# Sheet1.net
KiCad netlist of a schematic drawn in Altium Designer
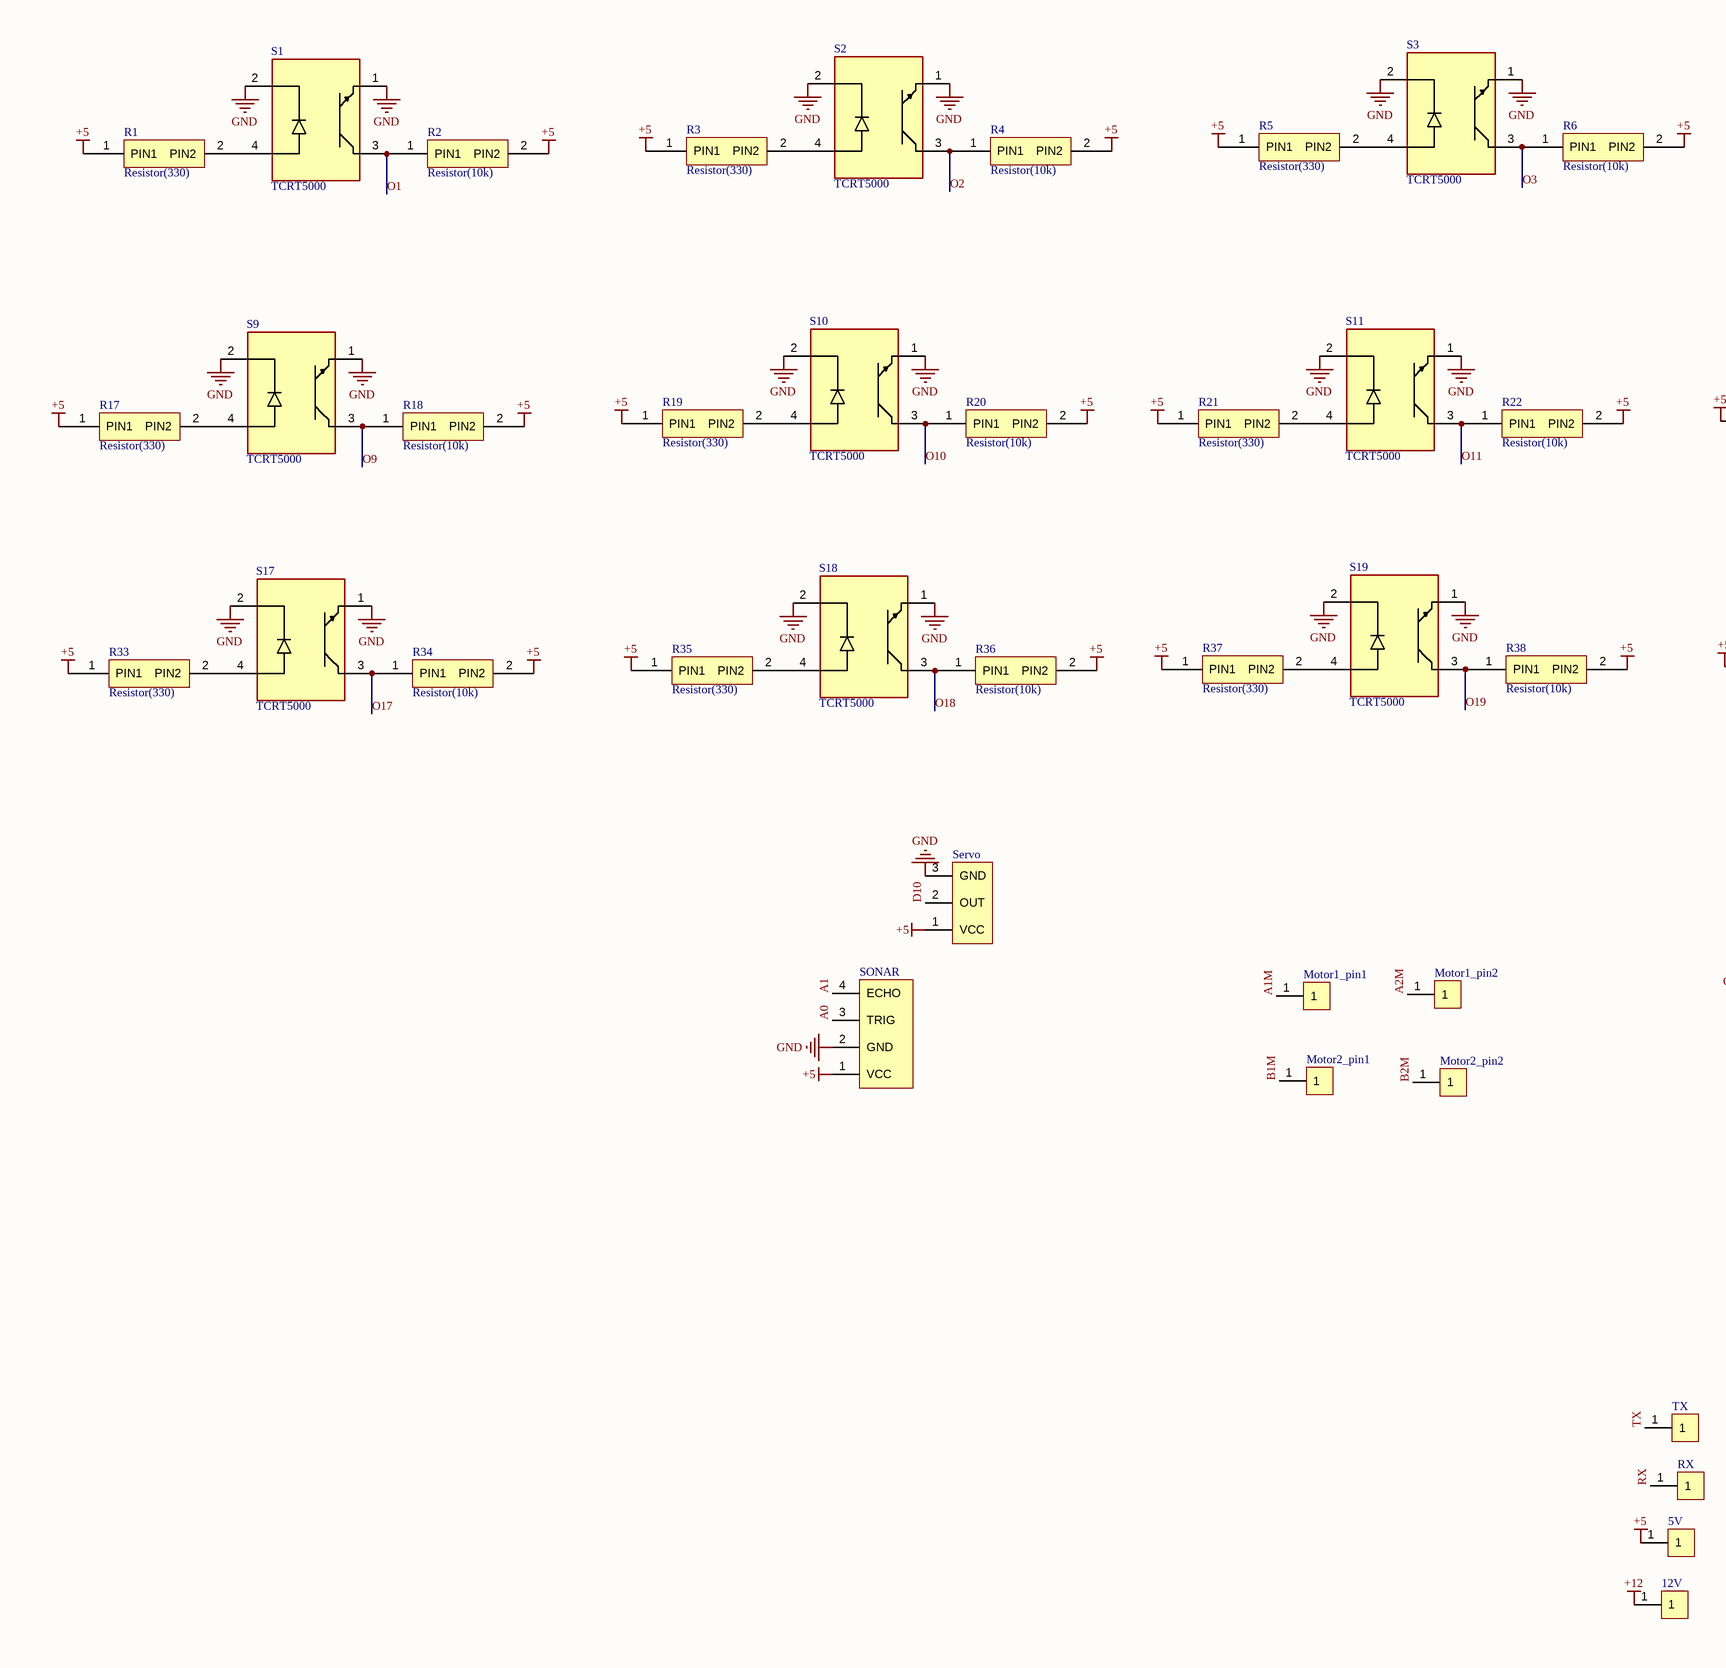
[diagram p0: Sheet1.SchDoc, left]
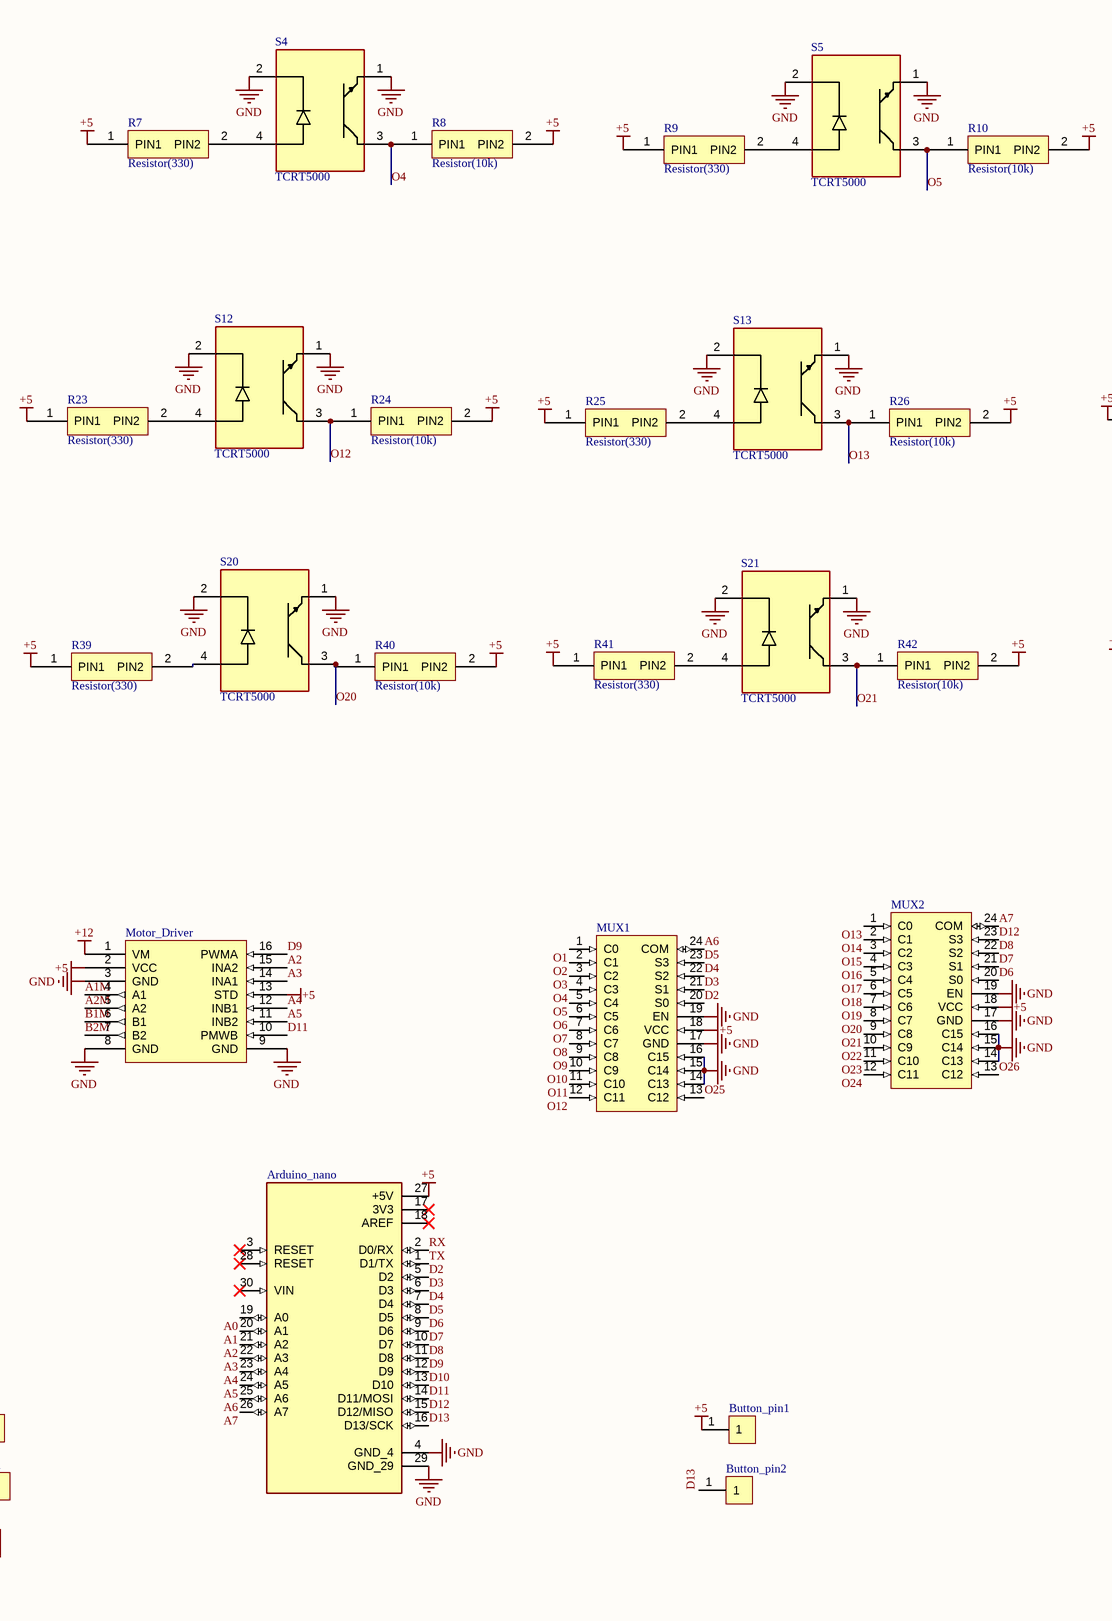
[diagram p1: Sheet1.SchDoc, middle]
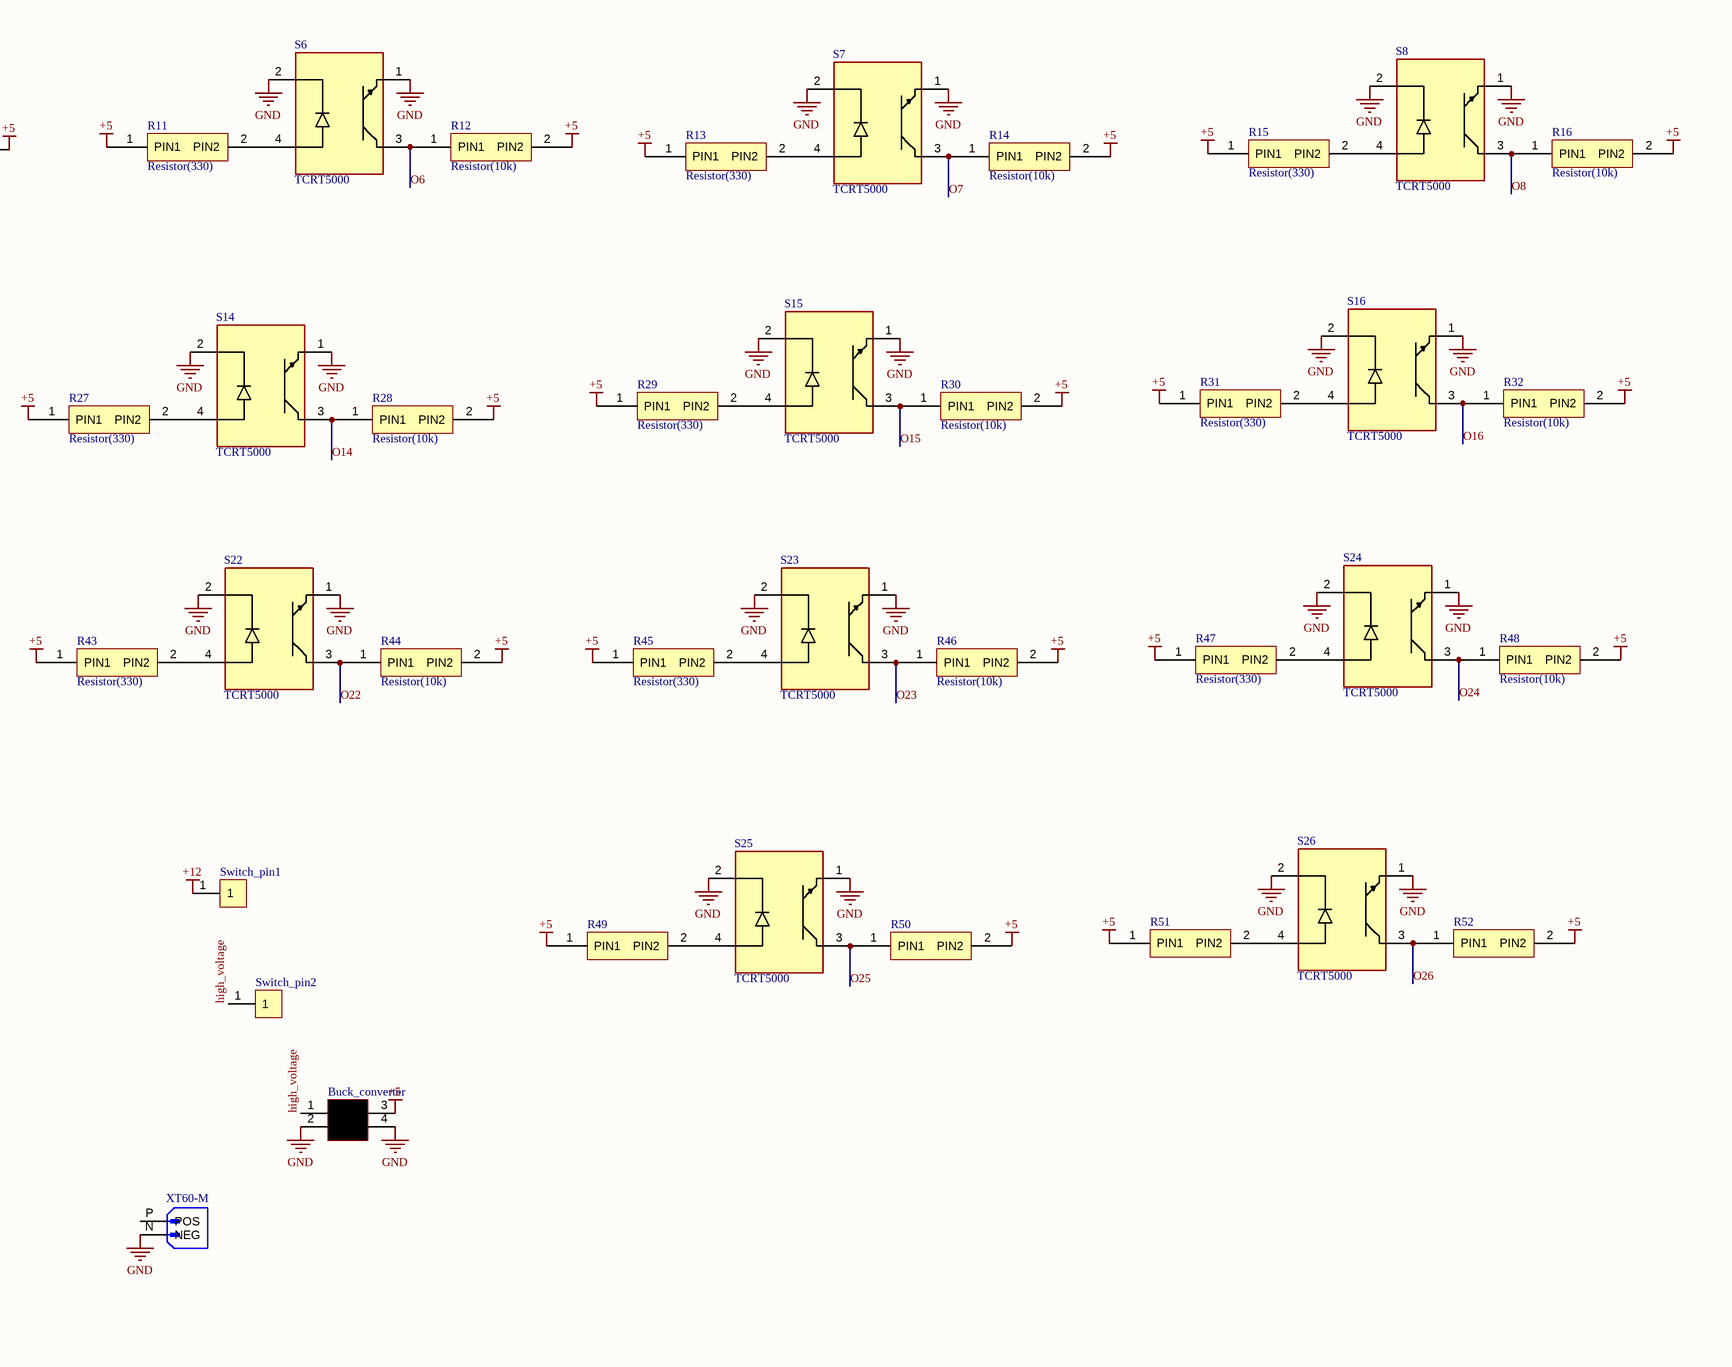
[diagram p2: Sheet1.SchDoc, right]

(export (version "E")
  (design (tool "Eeschema 10.0.6"))
  (components
    (comp (ref "5V")
      (value "~")
      (footprint "1_pin_male_header")
      (libsource (lib "newer") (part "1_pin_male_header"))
    )
    (comp (ref "12V")
      (value "~")
      (footprint "1_pin_male_header")
      (libsource (lib "newer") (part "1_pin_male_header"))
    )
    (comp (ref "Arduino_nano")
      (value "~")
      (footprint "Arduino_nano")
      (libsource (lib "newer") (part "Arduino_nano"))
    )
    (comp (ref "Buck_converter")
      (value "~")
      (footprint "Buck_converter")
      (libsource (lib "newer") (part "Buck_converter"))
    )
    (comp (ref "Button_pin1")
      (value "~")
      (footprint "1_pin_female_header")
      (libsource (lib "newer") (part "1_pin_female_header"))
    )
    (comp (ref "Button_pin2")
      (value "~")
      (footprint "1_pin_female_header")
      (libsource (lib "newer") (part "1_pin_female_header"))
    )
    (comp (ref "Motor1_pin1")
      (value "~")
      (footprint "1_pin_male_header")
      (libsource (lib "newer") (part "1_pin_male_header"))
    )
    (comp (ref "Motor1_pin2")
      (value "~")
      (footprint "1_pin_male_header")
      (libsource (lib "newer") (part "1_pin_male_header"))
    )
    (comp (ref "Motor2_pin1")
      (value "~")
      (footprint "1_pin_male_header")
      (libsource (lib "newer") (part "1_pin_male_header"))
    )
    (comp (ref "Motor2_pin2")
      (value "~")
      (footprint "1_pin_male_header")
      (libsource (lib "newer") (part "1_pin_male_header"))
    )
    (comp (ref "Motor_Driver")
      (value "~")
      (footprint "TB6612_Motor_driver")
      (libsource (lib "newer") (part "TB6612_Motor_driver"))
    )
    (comp (ref "MUX1") (value "~") (footprint "MUX") (libsource (lib "newer") (part "MUX")))
    (comp (ref "MUX2") (value "~") (footprint "MUX") (libsource (lib "newer") (part "MUX")))
    (comp (ref "R1")
      (value "Resistor(330)")
      (footprint "Resistor(330)")
      (libsource (lib "newer") (part "Resistor(330)"))
    )
    (comp (ref "R2")
      (value "Resistor(10k)")
      (footprint "Resistor(10k)")
      (libsource (lib "newer") (part "Resistor(10k)"))
    )
    (comp (ref "R3")
      (value "Resistor(330)")
      (footprint "Resistor(330)")
      (libsource (lib "newer") (part "Resistor(330)"))
    )
    (comp (ref "R4")
      (value "Resistor(10k)")
      (footprint "Resistor(10k)")
      (libsource (lib "newer") (part "Resistor(10k)"))
    )
    (comp (ref "R5")
      (value "Resistor(330)")
      (footprint "Resistor(330)")
      (libsource (lib "newer") (part "Resistor(330)"))
    )
    (comp (ref "R6")
      (value "Resistor(10k)")
      (footprint "Resistor(10k)")
      (libsource (lib "newer") (part "Resistor(10k)"))
    )
    (comp (ref "R7")
      (value "Resistor(330)")
      (footprint "Resistor(330)")
      (libsource (lib "newer") (part "Resistor(330)"))
    )
    (comp (ref "R8")
      (value "Resistor(10k)")
      (footprint "Resistor(10k)")
      (libsource (lib "newer") (part "Resistor(10k)"))
    )
    (comp (ref "R9")
      (value "Resistor(330)")
      (footprint "Resistor(330)")
      (libsource (lib "newer") (part "Resistor(330)"))
    )
    (comp (ref "R10")
      (value "Resistor(10k)")
      (footprint "Resistor(10k)")
      (libsource (lib "newer") (part "Resistor(10k)"))
    )
    (comp (ref "R11")
      (value "Resistor(330)")
      (footprint "Resistor(330)")
      (libsource (lib "newer") (part "Resistor(330)"))
    )
    (comp (ref "R12")
      (value "Resistor(10k)")
      (footprint "Resistor(10k)")
      (libsource (lib "newer") (part "Resistor(10k)"))
    )
    (comp (ref "R13")
      (value "Resistor(330)")
      (footprint "Resistor(330)")
      (libsource (lib "newer") (part "Resistor(330)"))
    )
    (comp (ref "R14")
      (value "Resistor(10k)")
      (footprint "Resistor(10k)")
      (libsource (lib "newer") (part "Resistor(10k)"))
    )
    (comp (ref "R15")
      (value "Resistor(330)")
      (footprint "Resistor(330)")
      (libsource (lib "newer") (part "Resistor(330)"))
    )
    (comp (ref "R16")
      (value "Resistor(10k)")
      (footprint "Resistor(10k)")
      (libsource (lib "newer") (part "Resistor(10k)"))
    )
    (comp (ref "R17")
      (value "Resistor(330)")
      (footprint "Resistor(330)")
      (libsource (lib "newer") (part "Resistor(330)"))
    )
    (comp (ref "R18")
      (value "Resistor(10k)")
      (footprint "Resistor(10k)")
      (libsource (lib "newer") (part "Resistor(10k)"))
    )
    (comp (ref "R19")
      (value "Resistor(330)")
      (footprint "Resistor(330)")
      (libsource (lib "newer") (part "Resistor(330)"))
    )
    (comp (ref "R20")
      (value "Resistor(10k)")
      (footprint "Resistor(10k)")
      (libsource (lib "newer") (part "Resistor(10k)"))
    )
    (comp (ref "R21")
      (value "Resistor(330)")
      (footprint "Resistor(330)")
      (libsource (lib "newer") (part "Resistor(330)"))
    )
    (comp (ref "R22")
      (value "Resistor(10k)")
      (footprint "Resistor(10k)")
      (libsource (lib "newer") (part "Resistor(10k)"))
    )
    (comp (ref "R23")
      (value "Resistor(330)")
      (footprint "Resistor(330)")
      (libsource (lib "newer") (part "Resistor(330)"))
    )
    (comp (ref "R24")
      (value "Resistor(10k)")
      (footprint "Resistor(10k)")
      (libsource (lib "newer") (part "Resistor(10k)"))
    )
    (comp (ref "R25")
      (value "Resistor(330)")
      (footprint "Resistor(330)")
      (libsource (lib "newer") (part "Resistor(330)"))
    )
    (comp (ref "R26")
      (value "Resistor(10k)")
      (footprint "Resistor(10k)")
      (libsource (lib "newer") (part "Resistor(10k)"))
    )
    (comp (ref "R27")
      (value "Resistor(330)")
      (footprint "Resistor(330)")
      (libsource (lib "newer") (part "Resistor(330)"))
    )
    (comp (ref "R28")
      (value "Resistor(10k)")
      (footprint "Resistor(10k)")
      (libsource (lib "newer") (part "Resistor(10k)"))
    )
    (comp (ref "R29")
      (value "Resistor(330)")
      (footprint "Resistor(330)")
      (libsource (lib "newer") (part "Resistor(330)"))
    )
    (comp (ref "R30")
      (value "Resistor(10k)")
      (footprint "Resistor(10k)")
      (libsource (lib "newer") (part "Resistor(10k)"))
    )
    (comp (ref "R31")
      (value "Resistor(330)")
      (footprint "Resistor(330)")
      (libsource (lib "newer") (part "Resistor(330)"))
    )
    (comp (ref "R32")
      (value "Resistor(10k)")
      (footprint "Resistor(10k)")
      (libsource (lib "newer") (part "Resistor(10k)"))
    )
    (comp (ref "R33")
      (value "Resistor(330)")
      (footprint "Resistor(330)")
      (libsource (lib "newer") (part "Resistor(330)"))
    )
    (comp (ref "R34")
      (value "Resistor(10k)")
      (footprint "Resistor(10k)")
      (libsource (lib "newer") (part "Resistor(10k)"))
    )
    (comp (ref "R35")
      (value "Resistor(330)")
      (footprint "Resistor(330)")
      (libsource (lib "newer") (part "Resistor(330)"))
    )
    (comp (ref "R36")
      (value "Resistor(10k)")
      (footprint "Resistor(10k)")
      (libsource (lib "newer") (part "Resistor(10k)"))
    )
    (comp (ref "R37")
      (value "Resistor(330)")
      (footprint "Resistor(330)")
      (libsource (lib "newer") (part "Resistor(330)"))
    )
    (comp (ref "R38")
      (value "Resistor(10k)")
      (footprint "Resistor(10k)")
      (libsource (lib "newer") (part "Resistor(10k)"))
    )
    (comp (ref "R39")
      (value "Resistor(330)")
      (footprint "Resistor(330)")
      (libsource (lib "newer") (part "Resistor(330)"))
    )
    (comp (ref "R40")
      (value "Resistor(10k)")
      (footprint "Resistor(10k)")
      (libsource (lib "newer") (part "Resistor(10k)"))
    )
    (comp (ref "R41")
      (value "Resistor(330)")
      (footprint "Resistor(330)")
      (libsource (lib "newer") (part "Resistor(330)"))
    )
    (comp (ref "R42")
      (value "Resistor(10k)")
      (footprint "Resistor(10k)")
      (libsource (lib "newer") (part "Resistor(10k)"))
    )
    (comp (ref "R43")
      (value "Resistor(330)")
      (footprint "Resistor(330)")
      (libsource (lib "newer") (part "Resistor(330)"))
    )
    (comp (ref "R44")
      (value "Resistor(10k)")
      (footprint "Resistor(10k)")
      (libsource (lib "newer") (part "Resistor(10k)"))
    )
    (comp (ref "R45")
      (value "Resistor(330)")
      (footprint "Resistor(330)")
      (libsource (lib "newer") (part "Resistor(330)"))
    )
    (comp (ref "R46")
      (value "Resistor(10k)")
      (footprint "Resistor(10k)")
      (libsource (lib "newer") (part "Resistor(10k)"))
    )
    (comp (ref "R47")
      (value "Resistor(330)")
      (footprint "Resistor(330)")
      (libsource (lib "newer") (part "Resistor(330)"))
    )
    (comp (ref "R48")
      (value "Resistor(10k)")
      (footprint "Resistor(10k)")
      (libsource (lib "newer") (part "Resistor(10k)"))
    )
    (comp (ref "R49")
      (value "~")
      (footprint "Resistor(330)")
      (libsource (lib "newer") (part "Resistor(330)"))
    )
    (comp (ref "R50")
      (value "~")
      (footprint "Resistor(10k)")
      (libsource (lib "newer") (part "Resistor(10k)"))
    )
    (comp (ref "R51")
      (value "~")
      (footprint "Resistor(330)")
      (libsource (lib "newer") (part "Resistor(330)"))
    )
    (comp (ref "R52")
      (value "~")
      (footprint "Resistor(10k)")
      (libsource (lib "newer") (part "Resistor(10k)"))
    )
    (comp (ref "RX")
      (value "~")
      (footprint "1_pin_male_header")
      (libsource (lib "newer") (part "1_pin_male_header"))
    )
    (comp (ref "S1") (value "TCRT5000") (footprint "TCRT5000") (libsource (lib "newer") (part "TCRT5000")))
    (comp (ref "S2") (value "TCRT5000") (footprint "TCRT5000") (libsource (lib "newer") (part "TCRT5000")))
    (comp (ref "S3") (value "TCRT5000") (footprint "TCRT5000") (libsource (lib "newer") (part "TCRT5000")))
    (comp (ref "S4") (value "TCRT5000") (footprint "TCRT5000") (libsource (lib "newer") (part "TCRT5000")))
    (comp (ref "S5") (value "TCRT5000") (footprint "TCRT5000") (libsource (lib "newer") (part "TCRT5000")))
    (comp (ref "S6") (value "TCRT5000") (footprint "TCRT5000") (libsource (lib "newer") (part "TCRT5000")))
    (comp (ref "S7") (value "TCRT5000") (footprint "TCRT5000") (libsource (lib "newer") (part "TCRT5000")))
    (comp (ref "S8") (value "TCRT5000") (footprint "TCRT5000") (libsource (lib "newer") (part "TCRT5000")))
    (comp (ref "S9") (value "TCRT5000") (footprint "TCRT5000") (libsource (lib "newer") (part "TCRT5000")))
    (comp (ref "S10") (value "TCRT5000") (footprint "TCRT5000") (libsource (lib "newer") (part "TCRT5000")))
    (comp (ref "S11") (value "TCRT5000") (footprint "TCRT5000") (libsource (lib "newer") (part "TCRT5000")))
    (comp (ref "S12") (value "TCRT5000") (footprint "TCRT5000") (libsource (lib "newer") (part "TCRT5000")))
    (comp (ref "S13") (value "TCRT5000") (footprint "TCRT5000") (libsource (lib "newer") (part "TCRT5000")))
    (comp (ref "S14") (value "TCRT5000") (footprint "TCRT5000") (libsource (lib "newer") (part "TCRT5000")))
    (comp (ref "S15") (value "TCRT5000") (footprint "TCRT5000") (libsource (lib "newer") (part "TCRT5000")))
    (comp (ref "S16") (value "TCRT5000") (footprint "TCRT5000") (libsource (lib "newer") (part "TCRT5000")))
    (comp (ref "S17") (value "TCRT5000") (footprint "TCRT5000") (libsource (lib "newer") (part "TCRT5000")))
    (comp (ref "S18") (value "TCRT5000") (footprint "TCRT5000") (libsource (lib "newer") (part "TCRT5000")))
    (comp (ref "S19") (value "TCRT5000") (footprint "TCRT5000") (libsource (lib "newer") (part "TCRT5000")))
    (comp (ref "S20") (value "TCRT5000") (footprint "TCRT5000") (libsource (lib "newer") (part "TCRT5000")))
    (comp (ref "S21") (value "TCRT5000") (footprint "TCRT5000") (libsource (lib "newer") (part "TCRT5000")))
    (comp (ref "S22") (value "TCRT5000") (footprint "TCRT5000") (libsource (lib "newer") (part "TCRT5000")))
    (comp (ref "S23") (value "TCRT5000") (footprint "TCRT5000") (libsource (lib "newer") (part "TCRT5000")))
    (comp (ref "S24") (value "TCRT5000") (footprint "TCRT5000") (libsource (lib "newer") (part "TCRT5000")))
    (comp (ref "S25") (value "TCRT5000") (footprint "TCRT5000") (libsource (lib "newer") (part "TCRT5000")))
    (comp (ref "S26") (value "TCRT5000") (footprint "TCRT5000") (libsource (lib "newer") (part "TCRT5000")))
    (comp (ref "Servo")
      (value "~")
      (footprint "3_pin_male_header")
      (libsource (lib "newer") (part "3_pin_male_header"))
    )
    (comp (ref "SONAR") (value "~") (footprint "4 pin male") (libsource (lib "lfr_nano") (part "4 pin male")))
    (comp (ref "Switch_pin1")
      (value "~")
      (footprint "1_pin_male_header")
      (libsource (lib "newer") (part "1_pin_male_header"))
    )
    (comp (ref "Switch_pin2")
      (value "~")
      (footprint "1_pin_male_header")
      (libsource (lib "newer") (part "1_pin_male_header"))
    )
    (comp (ref "TX")
      (value "~")
      (footprint "1_pin_male_header")
      (libsource (lib "newer") (part "1_pin_male_header"))
    )
    (comp (ref "XT60-M")
      (value "~")
      (footprint "AMASS_XT60-M")
      (description "Plug; DC supply; XT60; male; PIN: 2; for cable; soldered; 30A; 500V")
      (fields (field (name "MF") "AMASS") (field (name "MP") "XT60-M"))
      (libsource (lib "XT60-M") (part "XT60-M"))
    )
  )
  (nets
    (net (code "1") (name "+5") (class "Default")
      (node (ref "5V") (pin "1") (pinfunction "1_1") (pintype "passive"))
      (node (ref "Arduino_nano") (pin "27") (pinfunction "+5V_27") (pintype "power_in"))
      (node (ref "Buck_converter") (pin "3") (pinfunction "3_3") (pintype "passive"))
      (node (ref "Button_pin1") (pin "1") (pinfunction "1_1") (pintype "passive"))
      (node (ref "MUX1") (pin "18") (pinfunction "VCC_18") (pintype "input"))
      (node (ref "MUX2") (pin "18") (pinfunction "VCC_18") (pintype "input"))
      (node (ref "Motor_Driver") (pin "13") (pinfunction "STD_13") (pintype "input"))
      (node (ref "Motor_Driver") (pin "2") (pinfunction "VCC_2") (pintype "power_in"))
      (node (ref "R1") (pin "1") (pinfunction "PIN1_1") (pintype "passive"))
      (node (ref "R10") (pin "2") (pinfunction "PIN2_2") (pintype "passive"))
      (node (ref "R11") (pin "1") (pinfunction "PIN1_1") (pintype "passive"))
      (node (ref "R12") (pin "2") (pinfunction "PIN2_2") (pintype "passive"))
      (node (ref "R13") (pin "1") (pinfunction "PIN1_1") (pintype "passive"))
      (node (ref "R14") (pin "2") (pinfunction "PIN2_2") (pintype "passive"))
      (node (ref "R15") (pin "1") (pinfunction "PIN1_1") (pintype "passive"))
      (node (ref "R16") (pin "2") (pinfunction "PIN2_2") (pintype "passive"))
      (node (ref "R17") (pin "1") (pinfunction "PIN1_1") (pintype "passive"))
      (node (ref "R18") (pin "2") (pinfunction "PIN2_2") (pintype "passive"))
      (node (ref "R19") (pin "1") (pinfunction "PIN1_1") (pintype "passive"))
      (node (ref "R2") (pin "2") (pinfunction "PIN2_2") (pintype "passive"))
      (node (ref "R20") (pin "2") (pinfunction "PIN2_2") (pintype "passive"))
      (node (ref "R21") (pin "1") (pinfunction "PIN1_1") (pintype "passive"))
      (node (ref "R22") (pin "2") (pinfunction "PIN2_2") (pintype "passive"))
      (node (ref "R23") (pin "1") (pinfunction "PIN1_1") (pintype "passive"))
      (node (ref "R24") (pin "2") (pinfunction "PIN2_2") (pintype "passive"))
      (node (ref "R25") (pin "1") (pinfunction "PIN1_1") (pintype "passive"))
      (node (ref "R26") (pin "2") (pinfunction "PIN2_2") (pintype "passive"))
      (node (ref "R27") (pin "1") (pinfunction "PIN1_1") (pintype "passive"))
      (node (ref "R28") (pin "2") (pinfunction "PIN2_2") (pintype "passive"))
      (node (ref "R29") (pin "1") (pinfunction "PIN1_1") (pintype "passive"))
      (node (ref "R3") (pin "1") (pinfunction "PIN1_1") (pintype "passive"))
      (node (ref "R30") (pin "2") (pinfunction "PIN2_2") (pintype "passive"))
      (node (ref "R31") (pin "1") (pinfunction "PIN1_1") (pintype "passive"))
      (node (ref "R32") (pin "2") (pinfunction "PIN2_2") (pintype "passive"))
      (node (ref "R33") (pin "1") (pinfunction "PIN1_1") (pintype "passive"))
      (node (ref "R34") (pin "2") (pinfunction "PIN2_2") (pintype "passive"))
      (node (ref "R35") (pin "1") (pinfunction "PIN1_1") (pintype "passive"))
      (node (ref "R36") (pin "2") (pinfunction "PIN2_2") (pintype "passive"))
      (node (ref "R37") (pin "1") (pinfunction "PIN1_1") (pintype "passive"))
      (node (ref "R38") (pin "2") (pinfunction "PIN2_2") (pintype "passive"))
      (node (ref "R39") (pin "1") (pinfunction "PIN1_1") (pintype "passive"))
      (node (ref "R4") (pin "2") (pinfunction "PIN2_2") (pintype "passive"))
      (node (ref "R40") (pin "2") (pinfunction "PIN2_2") (pintype "passive"))
      (node (ref "R41") (pin "1") (pinfunction "PIN1_1") (pintype "passive"))
      (node (ref "R42") (pin "2") (pinfunction "PIN2_2") (pintype "passive"))
      (node (ref "R43") (pin "1") (pinfunction "PIN1_1") (pintype "passive"))
      (node (ref "R44") (pin "2") (pinfunction "PIN2_2") (pintype "passive"))
      (node (ref "R45") (pin "1") (pinfunction "PIN1_1") (pintype "passive"))
      (node (ref "R46") (pin "2") (pinfunction "PIN2_2") (pintype "passive"))
      (node (ref "R47") (pin "1") (pinfunction "PIN1_1") (pintype "passive"))
      (node (ref "R48") (pin "2") (pinfunction "PIN2_2") (pintype "passive"))
      (node (ref "R49") (pin "1") (pinfunction "PIN1_1") (pintype "passive"))
      (node (ref "R5") (pin "1") (pinfunction "PIN1_1") (pintype "passive"))
      (node (ref "R50") (pin "2") (pinfunction "PIN2_2") (pintype "passive"))
      (node (ref "R51") (pin "1") (pinfunction "PIN1_1") (pintype "passive"))
      (node (ref "R52") (pin "2") (pinfunction "PIN2_2") (pintype "passive"))
      (node (ref "R6") (pin "2") (pinfunction "PIN2_2") (pintype "passive"))
      (node (ref "R7") (pin "1") (pinfunction "PIN1_1") (pintype "passive"))
      (node (ref "R8") (pin "2") (pinfunction "PIN2_2") (pintype "passive"))
      (node (ref "R9") (pin "1") (pinfunction "PIN1_1") (pintype "passive"))
      (node (ref "SONAR") (pin "1") (pinfunction "VCC_1") (pintype "passive"))
      (node (ref "Servo") (pin "1") (pinfunction "VCC_1") (pintype "passive"))
    )
    (net (code "2") (name "+12") (class "Default")
      (node (ref "12V") (pin "1") (pinfunction "1_1") (pintype "passive"))
      (node (ref "Motor_Driver") (pin "1") (pinfunction "VM_1") (pintype "power_in"))
      (node (ref "Switch_pin1") (pin "1") (pinfunction "1_1") (pintype "passive"))
    )
    (net (code "3") (name "/A0") (class "Default")
      (node (ref "Arduino_nano") (pin "19") (pinfunction "A0_19") (pintype "bidirectional"))
      (node (ref "SONAR") (pin "3") (pinfunction "TRIG_3") (pintype "passive"))
    )
    (net (code "4") (name "/A1") (class "Default")
      (node (ref "Arduino_nano") (pin "20") (pinfunction "A1_20") (pintype "bidirectional"))
      (node (ref "SONAR") (pin "4") (pinfunction "ECHO_4") (pintype "passive"))
    )
    (net (code "5") (name "/A1M") (class "Default")
      (node (ref "Motor1_pin1") (pin "1") (pinfunction "1_1") (pintype "passive"))
      (node (ref "Motor_Driver") (pin "4") (pinfunction "A1_4") (pintype "output"))
    )
    (net (code "6") (name "/A2") (class "Default")
      (node (ref "Arduino_nano") (pin "21") (pinfunction "A2_21") (pintype "bidirectional"))
      (node (ref "Motor_Driver") (pin "15") (pinfunction "INA2_15") (pintype "input"))
    )
    (net (code "7") (name "/A2M") (class "Default")
      (node (ref "Motor1_pin2") (pin "1") (pinfunction "1_1") (pintype "passive"))
      (node (ref "Motor_Driver") (pin "5") (pinfunction "A2_5") (pintype "output"))
    )
    (net (code "8") (name "/A3") (class "Default")
      (node (ref "Arduino_nano") (pin "22") (pinfunction "A3_22") (pintype "bidirectional"))
      (node (ref "Motor_Driver") (pin "14") (pinfunction "INA1_14") (pintype "input"))
    )
    (net (code "9") (name "/A4") (class "Default")
      (node (ref "Arduino_nano") (pin "23") (pinfunction "A4_23") (pintype "bidirectional"))
      (node (ref "Motor_Driver") (pin "12") (pinfunction "INB1_12") (pintype "input"))
    )
    (net (code "10") (name "/A5") (class "Default")
      (node (ref "Arduino_nano") (pin "24") (pinfunction "A5_24") (pintype "bidirectional"))
      (node (ref "Motor_Driver") (pin "11") (pinfunction "INB2_11") (pintype "input"))
    )
    (net (code "11") (name "/A6") (class "Default")
      (node (ref "Arduino_nano") (pin "25") (pinfunction "A6_25") (pintype "bidirectional"))
      (node (ref "MUX1") (pin "24") (pinfunction "COM_24") (pintype "bidirectional"))
    )
    (net (code "12") (name "/A7") (class "Default")
      (node (ref "Arduino_nano") (pin "26") (pinfunction "A7_26") (pintype "bidirectional"))
      (node (ref "MUX2") (pin "24") (pinfunction "COM_24") (pintype "bidirectional"))
    )
    (net (code "13") (name "/B1M") (class "Default")
      (node (ref "Motor2_pin1") (pin "1") (pinfunction "1_1") (pintype "passive"))
      (node (ref "Motor_Driver") (pin "6") (pinfunction "B1_6") (pintype "output"))
    )
    (net (code "14") (name "/B2M") (class "Default")
      (node (ref "Motor2_pin2") (pin "1") (pinfunction "1_1") (pintype "passive"))
      (node (ref "Motor_Driver") (pin "7") (pinfunction "B2_7") (pintype "output"))
    )
    (net (code "15") (name "/D2") (class "Default")
      (node (ref "Arduino_nano") (pin "5") (pinfunction "D2_5") (pintype "bidirectional"))
      (node (ref "MUX1") (pin "20") (pinfunction "S0_20") (pintype "input"))
    )
    (net (code "16") (name "/D3") (class "Default")
      (node (ref "Arduino_nano") (pin "6") (pinfunction "D3_6") (pintype "bidirectional"))
      (node (ref "MUX1") (pin "21") (pinfunction "S1_21") (pintype "input"))
    )
    (net (code "17") (name "/D4") (class "Default")
      (node (ref "Arduino_nano") (pin "7") (pinfunction "D4_7") (pintype "bidirectional"))
      (node (ref "MUX1") (pin "22") (pinfunction "S2_22") (pintype "input"))
    )
    (net (code "18") (name "/D5") (class "Default")
      (node (ref "Arduino_nano") (pin "8") (pinfunction "D5_8") (pintype "bidirectional"))
      (node (ref "MUX1") (pin "23") (pinfunction "S3_23") (pintype "input"))
    )
    (net (code "19") (name "/D6") (class "Default")
      (node (ref "Arduino_nano") (pin "9") (pinfunction "D6_9") (pintype "bidirectional"))
      (node (ref "MUX2") (pin "20") (pinfunction "S0_20") (pintype "input"))
    )
    (net (code "20") (name "/D7") (class "Default")
      (node (ref "Arduino_nano") (pin "10") (pinfunction "D7_10") (pintype "bidirectional"))
      (node (ref "MUX2") (pin "21") (pinfunction "S1_21") (pintype "input"))
    )
    (net (code "21") (name "/D8") (class "Default")
      (node (ref "Arduino_nano") (pin "11") (pinfunction "D8_11") (pintype "bidirectional"))
      (node (ref "MUX2") (pin "22") (pinfunction "S2_22") (pintype "input"))
    )
    (net (code "22") (name "/D9") (class "Default")
      (node (ref "Arduino_nano") (pin "12") (pinfunction "D9_12") (pintype "bidirectional"))
      (node (ref "Motor_Driver") (pin "16") (pinfunction "PWMA_16") (pintype "input"))
    )
    (net (code "23") (name "/D10") (class "Default")
      (node (ref "Arduino_nano") (pin "13") (pinfunction "D10_13") (pintype "bidirectional"))
      (node (ref "Servo") (pin "2") (pinfunction "OUT_2") (pintype "passive"))
    )
    (net (code "24") (name "/D11") (class "Default")
      (node (ref "Arduino_nano") (pin "14") (pinfunction "D11/MOSI_14") (pintype "bidirectional"))
      (node (ref "Motor_Driver") (pin "10") (pinfunction "PMWB_10") (pintype "input"))
    )
    (net (code "25") (name "/D12") (class "Default")
      (node (ref "Arduino_nano") (pin "15") (pinfunction "D12/MISO_15") (pintype "bidirectional"))
      (node (ref "MUX2") (pin "23") (pinfunction "S3_23") (pintype "input"))
    )
    (net (code "26") (name "/D13") (class "Default")
      (node (ref "Arduino_nano") (pin "16") (pinfunction "D13/SCK_16") (pintype "bidirectional"))
      (node (ref "Button_pin2") (pin "1") (pinfunction "1_1") (pintype "passive"))
    )
    (net (code "27") (name "/O1") (class "Default")
      (node (ref "MUX1") (pin "1") (pinfunction "C0_1") (pintype "input"))
      (node (ref "R2") (pin "1") (pinfunction "PIN1_1") (pintype "passive"))
      (node (ref "S1") (pin "3") (pinfunction "collector_3") (pintype "passive"))
    )
    (net (code "28") (name "/O2") (class "Default")
      (node (ref "MUX1") (pin "2") (pinfunction "C1_2") (pintype "input"))
      (node (ref "R4") (pin "1") (pinfunction "PIN1_1") (pintype "passive"))
      (node (ref "S2") (pin "3") (pinfunction "collector_3") (pintype "passive"))
    )
    (net (code "29") (name "/O3") (class "Default")
      (node (ref "MUX1") (pin "3") (pinfunction "C2_3") (pintype "input"))
      (node (ref "R6") (pin "1") (pinfunction "PIN1_1") (pintype "passive"))
      (node (ref "S3") (pin "3") (pinfunction "collector_3") (pintype "passive"))
    )
    (net (code "30") (name "/O4") (class "Default")
      (node (ref "MUX1") (pin "4") (pinfunction "C3_4") (pintype "input"))
      (node (ref "R8") (pin "1") (pinfunction "PIN1_1") (pintype "passive"))
      (node (ref "S4") (pin "3") (pinfunction "collector_3") (pintype "passive"))
    )
    (net (code "31") (name "/O5") (class "Default")
      (node (ref "MUX1") (pin "5") (pinfunction "C4_5") (pintype "input"))
      (node (ref "R10") (pin "1") (pinfunction "PIN1_1") (pintype "passive"))
      (node (ref "S5") (pin "3") (pinfunction "collector_3") (pintype "passive"))
    )
    (net (code "32") (name "/O6") (class "Default")
      (node (ref "MUX1") (pin "6") (pinfunction "C5_6") (pintype "input"))
      (node (ref "R12") (pin "1") (pinfunction "PIN1_1") (pintype "passive"))
      (node (ref "S6") (pin "3") (pinfunction "collector_3") (pintype "passive"))
    )
    (net (code "33") (name "/O7") (class "Default")
      (node (ref "MUX1") (pin "7") (pinfunction "C6_7") (pintype "input"))
      (node (ref "R14") (pin "1") (pinfunction "PIN1_1") (pintype "passive"))
      (node (ref "S7") (pin "3") (pinfunction "collector_3") (pintype "passive"))
    )
    (net (code "34") (name "/O8") (class "Default")
      (node (ref "MUX1") (pin "8") (pinfunction "C7_8") (pintype "input"))
      (node (ref "R16") (pin "1") (pinfunction "PIN1_1") (pintype "passive"))
      (node (ref "S8") (pin "3") (pinfunction "collector_3") (pintype "passive"))
    )
    (net (code "35") (name "/O9") (class "Default")
      (node (ref "MUX1") (pin "9") (pinfunction "C8_9") (pintype "input"))
      (node (ref "R18") (pin "1") (pinfunction "PIN1_1") (pintype "passive"))
      (node (ref "S9") (pin "3") (pinfunction "collector_3") (pintype "passive"))
    )
    (net (code "36") (name "/O10") (class "Default")
      (node (ref "MUX1") (pin "10") (pinfunction "C9_10") (pintype "input"))
      (node (ref "R20") (pin "1") (pinfunction "PIN1_1") (pintype "passive"))
      (node (ref "S10") (pin "3") (pinfunction "collector_3") (pintype "passive"))
    )
    (net (code "37") (name "/O11") (class "Default")
      (node (ref "MUX1") (pin "11") (pinfunction "C10_11") (pintype "input"))
      (node (ref "R22") (pin "1") (pinfunction "PIN1_1") (pintype "passive"))
      (node (ref "S11") (pin "3") (pinfunction "collector_3") (pintype "passive"))
    )
    (net (code "38") (name "/O12") (class "Default")
      (node (ref "MUX1") (pin "12") (pinfunction "C11_12") (pintype "input"))
      (node (ref "R24") (pin "1") (pinfunction "PIN1_1") (pintype "passive"))
      (node (ref "S12") (pin "3") (pinfunction "collector_3") (pintype "passive"))
    )
    (net (code "39") (name "/O13") (class "Default")
      (node (ref "MUX2") (pin "1") (pinfunction "C0_1") (pintype "input"))
      (node (ref "R26") (pin "1") (pinfunction "PIN1_1") (pintype "passive"))
      (node (ref "S13") (pin "3") (pinfunction "collector_3") (pintype "passive"))
    )
    (net (code "40") (name "/O14") (class "Default")
      (node (ref "MUX2") (pin "2") (pinfunction "C1_2") (pintype "input"))
      (node (ref "R28") (pin "1") (pinfunction "PIN1_1") (pintype "passive"))
      (node (ref "S14") (pin "3") (pinfunction "collector_3") (pintype "passive"))
    )
    (net (code "41") (name "/O15") (class "Default")
      (node (ref "MUX2") (pin "3") (pinfunction "C2_3") (pintype "input"))
      (node (ref "R30") (pin "1") (pinfunction "PIN1_1") (pintype "passive"))
      (node (ref "S15") (pin "3") (pinfunction "collector_3") (pintype "passive"))
    )
    (net (code "42") (name "/O16") (class "Default")
      (node (ref "MUX2") (pin "4") (pinfunction "C3_4") (pintype "input"))
      (node (ref "R32") (pin "1") (pinfunction "PIN1_1") (pintype "passive"))
      (node (ref "S16") (pin "3") (pinfunction "collector_3") (pintype "passive"))
    )
    (net (code "43") (name "/O17") (class "Default")
      (node (ref "MUX2") (pin "5") (pinfunction "C4_5") (pintype "input"))
      (node (ref "R34") (pin "1") (pinfunction "PIN1_1") (pintype "passive"))
      (node (ref "S17") (pin "3") (pinfunction "collector_3") (pintype "passive"))
    )
    (net (code "44") (name "/O18") (class "Default")
      (node (ref "MUX2") (pin "6") (pinfunction "C5_6") (pintype "input"))
      (node (ref "R36") (pin "1") (pinfunction "PIN1_1") (pintype "passive"))
      (node (ref "S18") (pin "3") (pinfunction "collector_3") (pintype "passive"))
    )
    (net (code "45") (name "/O19") (class "Default")
      (node (ref "MUX2") (pin "7") (pinfunction "C6_7") (pintype "input"))
      (node (ref "R38") (pin "1") (pinfunction "PIN1_1") (pintype "passive"))
      (node (ref "S19") (pin "3") (pinfunction "collector_3") (pintype "passive"))
    )
    (net (code "46") (name "/O20") (class "Default")
      (node (ref "MUX2") (pin "8") (pinfunction "C7_8") (pintype "input"))
      (node (ref "R40") (pin "1") (pinfunction "PIN1_1") (pintype "passive"))
      (node (ref "S20") (pin "3") (pinfunction "collector_3") (pintype "passive"))
    )
    (net (code "47") (name "/O21") (class "Default")
      (node (ref "MUX2") (pin "9") (pinfunction "C8_9") (pintype "input"))
      (node (ref "R42") (pin "1") (pinfunction "PIN1_1") (pintype "passive"))
      (node (ref "S21") (pin "3") (pinfunction "collector_3") (pintype "passive"))
    )
    (net (code "48") (name "/O22") (class "Default")
      (node (ref "MUX2") (pin "10") (pinfunction "C9_10") (pintype "input"))
      (node (ref "R44") (pin "1") (pinfunction "PIN1_1") (pintype "passive"))
      (node (ref "S22") (pin "3") (pinfunction "collector_3") (pintype "passive"))
    )
    (net (code "49") (name "/O23") (class "Default")
      (node (ref "MUX2") (pin "11") (pinfunction "C10_11") (pintype "input"))
      (node (ref "R46") (pin "1") (pinfunction "PIN1_1") (pintype "passive"))
      (node (ref "S23") (pin "3") (pinfunction "collector_3") (pintype "passive"))
    )
    (net (code "50") (name "/O24") (class "Default")
      (node (ref "MUX2") (pin "12") (pinfunction "C11_12") (pintype "input"))
      (node (ref "R48") (pin "1") (pinfunction "PIN1_1") (pintype "passive"))
      (node (ref "S24") (pin "3") (pinfunction "collector_3") (pintype "passive"))
    )
    (net (code "51") (name "/O25") (class "Default")
      (node (ref "MUX1") (pin "13") (pinfunction "C12_13") (pintype "input"))
      (node (ref "R50") (pin "1") (pinfunction "PIN1_1") (pintype "passive"))
      (node (ref "S25") (pin "3") (pinfunction "collector_3") (pintype "passive"))
    )
    (net (code "52") (name "/O26") (class "Default")
      (node (ref "MUX2") (pin "13") (pinfunction "C12_13") (pintype "input"))
      (node (ref "R52") (pin "1") (pinfunction "PIN1_1") (pintype "passive"))
      (node (ref "S26") (pin "3") (pinfunction "collector_3") (pintype "passive"))
    )
    (net (code "53") (name "/RX") (class "Default")
      (node (ref "Arduino_nano") (pin "2") (pinfunction "D0/RX_2") (pintype "bidirectional"))
      (node (ref "RX") (pin "1") (pinfunction "1_1") (pintype "passive"))
    )
    (net (code "54") (name "/TX") (class "Default")
      (node (ref "Arduino_nano") (pin "1") (pinfunction "D1/TX_1") (pintype "bidirectional"))
      (node (ref "TX") (pin "1") (pinfunction "1_1") (pintype "passive"))
    )
    (net (code "55") (name "/high_voltage") (class "Default")
      (node (ref "Buck_converter") (pin "1") (pinfunction "1_1") (pintype "passive"))
      (node (ref "Switch_pin2") (pin "1") (pinfunction "1_1") (pintype "passive"))
    )
    (net (code "56") (name "GND") (class "Default")
      (node (ref "Arduino_nano") (pin "29") (pinfunction "GND_29_29") (pintype "power_in"))
      (node (ref "Arduino_nano") (pin "4") (pinfunction "GND_4_4") (pintype "power_in"))
      (node (ref "Buck_converter") (pin "2") (pinfunction "2_2") (pintype "passive"))
      (node (ref "Buck_converter") (pin "4") (pinfunction "4_4") (pintype "passive"))
      (node (ref "MUX1") (pin "14") (pinfunction "C13_14") (pintype "input"))
      (node (ref "MUX1") (pin "15") (pinfunction "C14_15") (pintype "input"))
      (node (ref "MUX1") (pin "16") (pinfunction "C15_16") (pintype "input"))
      (node (ref "MUX1") (pin "17") (pinfunction "GND_17") (pintype "power_in"))
      (node (ref "MUX1") (pin "19") (pinfunction "EN_19") (pintype "power_in"))
      (node (ref "MUX2") (pin "14") (pinfunction "C13_14") (pintype "input"))
      (node (ref "MUX2") (pin "15") (pinfunction "C14_15") (pintype "input"))
      (node (ref "MUX2") (pin "16") (pinfunction "C15_16") (pintype "input"))
      (node (ref "MUX2") (pin "17") (pinfunction "GND_17") (pintype "power_in"))
      (node (ref "MUX2") (pin "19") (pinfunction "EN_19") (pintype "power_in"))
      (node (ref "Motor_Driver") (pin "3") (pinfunction "GND_3") (pintype "power_in"))
      (node (ref "Motor_Driver") (pin "8") (pinfunction "GND_8") (pintype "power_in"))
      (node (ref "Motor_Driver") (pin "9") (pinfunction "GND_9") (pintype "power_in"))
      (node (ref "S1") (pin "1") (pinfunction "emmiter_1") (pintype "passive"))
      (node (ref "S1") (pin "2") (pinfunction "cathode_2") (pintype "passive"))
      (node (ref "S10") (pin "1") (pinfunction "emmiter_1") (pintype "passive"))
      (node (ref "S10") (pin "2") (pinfunction "cathode_2") (pintype "passive"))
      (node (ref "S11") (pin "1") (pinfunction "emmiter_1") (pintype "passive"))
      (node (ref "S11") (pin "2") (pinfunction "cathode_2") (pintype "passive"))
      (node (ref "S12") (pin "1") (pinfunction "emmiter_1") (pintype "passive"))
      (node (ref "S12") (pin "2") (pinfunction "cathode_2") (pintype "passive"))
      (node (ref "S13") (pin "1") (pinfunction "emmiter_1") (pintype "passive"))
      (node (ref "S13") (pin "2") (pinfunction "cathode_2") (pintype "passive"))
      (node (ref "S14") (pin "1") (pinfunction "emmiter_1") (pintype "passive"))
      (node (ref "S14") (pin "2") (pinfunction "cathode_2") (pintype "passive"))
      (node (ref "S15") (pin "1") (pinfunction "emmiter_1") (pintype "passive"))
      (node (ref "S15") (pin "2") (pinfunction "cathode_2") (pintype "passive"))
      (node (ref "S16") (pin "1") (pinfunction "emmiter_1") (pintype "passive"))
      (node (ref "S16") (pin "2") (pinfunction "cathode_2") (pintype "passive"))
      (node (ref "S17") (pin "1") (pinfunction "emmiter_1") (pintype "passive"))
      (node (ref "S17") (pin "2") (pinfunction "cathode_2") (pintype "passive"))
      (node (ref "S18") (pin "1") (pinfunction "emmiter_1") (pintype "passive"))
      (node (ref "S18") (pin "2") (pinfunction "cathode_2") (pintype "passive"))
      (node (ref "S19") (pin "1") (pinfunction "emmiter_1") (pintype "passive"))
      (node (ref "S19") (pin "2") (pinfunction "cathode_2") (pintype "passive"))
      (node (ref "S2") (pin "1") (pinfunction "emmiter_1") (pintype "passive"))
      (node (ref "S2") (pin "2") (pinfunction "cathode_2") (pintype "passive"))
      (node (ref "S20") (pin "1") (pinfunction "emmiter_1") (pintype "passive"))
      (node (ref "S20") (pin "2") (pinfunction "cathode_2") (pintype "passive"))
      (node (ref "S21") (pin "1") (pinfunction "emmiter_1") (pintype "passive"))
      (node (ref "S21") (pin "2") (pinfunction "cathode_2") (pintype "passive"))
      (node (ref "S22") (pin "1") (pinfunction "emmiter_1") (pintype "passive"))
      (node (ref "S22") (pin "2") (pinfunction "cathode_2") (pintype "passive"))
      (node (ref "S23") (pin "1") (pinfunction "emmiter_1") (pintype "passive"))
      (node (ref "S23") (pin "2") (pinfunction "cathode_2") (pintype "passive"))
      (node (ref "S24") (pin "1") (pinfunction "emmiter_1") (pintype "passive"))
      (node (ref "S24") (pin "2") (pinfunction "cathode_2") (pintype "passive"))
      (node (ref "S25") (pin "1") (pinfunction "emmiter_1") (pintype "passive"))
      (node (ref "S25") (pin "2") (pinfunction "cathode_2") (pintype "passive"))
      (node (ref "S26") (pin "1") (pinfunction "emmiter_1") (pintype "passive"))
      (node (ref "S26") (pin "2") (pinfunction "cathode_2") (pintype "passive"))
      (node (ref "S3") (pin "1") (pinfunction "emmiter_1") (pintype "passive"))
      (node (ref "S3") (pin "2") (pinfunction "cathode_2") (pintype "passive"))
      (node (ref "S4") (pin "1") (pinfunction "emmiter_1") (pintype "passive"))
      (node (ref "S4") (pin "2") (pinfunction "cathode_2") (pintype "passive"))
      (node (ref "S5") (pin "1") (pinfunction "emmiter_1") (pintype "passive"))
      (node (ref "S5") (pin "2") (pinfunction "cathode_2") (pintype "passive"))
      (node (ref "S6") (pin "1") (pinfunction "emmiter_1") (pintype "passive"))
      (node (ref "S6") (pin "2") (pinfunction "cathode_2") (pintype "passive"))
      (node (ref "S7") (pin "1") (pinfunction "emmiter_1") (pintype "passive"))
      (node (ref "S7") (pin "2") (pinfunction "cathode_2") (pintype "passive"))
      (node (ref "S8") (pin "1") (pinfunction "emmiter_1") (pintype "passive"))
      (node (ref "S8") (pin "2") (pinfunction "cathode_2") (pintype "passive"))
      (node (ref "S9") (pin "1") (pinfunction "emmiter_1") (pintype "passive"))
      (node (ref "S9") (pin "2") (pinfunction "cathode_2") (pintype "passive"))
      (node (ref "SONAR") (pin "2") (pinfunction "GND_2") (pintype "passive"))
      (node (ref "Servo") (pin "3") (pinfunction "GND_3") (pintype "passive"))
      (node (ref "XT60-M") (pin "N") (pinfunction "NEG_N") (pintype "passive"))
    )
    (net (code "57") (name "Net-(R1-PIN2)") (class "Default")
      (node (ref "R1") (pin "2") (pinfunction "PIN2_2") (pintype "passive"))
      (node (ref "S1") (pin "4") (pinfunction "anode_4") (pintype "passive"))
    )
    (net (code "58") (name "Net-(R3-PIN2)") (class "Default")
      (node (ref "R3") (pin "2") (pinfunction "PIN2_2") (pintype "passive"))
      (node (ref "S2") (pin "4") (pinfunction "anode_4") (pintype "passive"))
    )
    (net (code "59") (name "Net-(R5-PIN2)") (class "Default")
      (node (ref "R5") (pin "2") (pinfunction "PIN2_2") (pintype "passive"))
      (node (ref "S3") (pin "4") (pinfunction "anode_4") (pintype "passive"))
    )
    (net (code "60") (name "Net-(R7-PIN2)") (class "Default")
      (node (ref "R7") (pin "2") (pinfunction "PIN2_2") (pintype "passive"))
      (node (ref "S4") (pin "4") (pinfunction "anode_4") (pintype "passive"))
    )
    (net (code "61") (name "Net-(R9-PIN2)") (class "Default")
      (node (ref "R9") (pin "2") (pinfunction "PIN2_2") (pintype "passive"))
      (node (ref "S5") (pin "4") (pinfunction "anode_4") (pintype "passive"))
    )
    (net (code "62") (name "Net-(R11-PIN2)") (class "Default")
      (node (ref "R11") (pin "2") (pinfunction "PIN2_2") (pintype "passive"))
      (node (ref "S6") (pin "4") (pinfunction "anode_4") (pintype "passive"))
    )
    (net (code "63") (name "Net-(R13-PIN2)") (class "Default")
      (node (ref "R13") (pin "2") (pinfunction "PIN2_2") (pintype "passive"))
      (node (ref "S7") (pin "4") (pinfunction "anode_4") (pintype "passive"))
    )
    (net (code "64") (name "Net-(R15-PIN2)") (class "Default")
      (node (ref "R15") (pin "2") (pinfunction "PIN2_2") (pintype "passive"))
      (node (ref "S8") (pin "4") (pinfunction "anode_4") (pintype "passive"))
    )
    (net (code "65") (name "Net-(R17-PIN2)") (class "Default")
      (node (ref "R17") (pin "2") (pinfunction "PIN2_2") (pintype "passive"))
      (node (ref "S9") (pin "4") (pinfunction "anode_4") (pintype "passive"))
    )
    (net (code "66") (name "Net-(R19-PIN2)") (class "Default")
      (node (ref "R19") (pin "2") (pinfunction "PIN2_2") (pintype "passive"))
      (node (ref "S10") (pin "4") (pinfunction "anode_4") (pintype "passive"))
    )
    (net (code "67") (name "Net-(R21-PIN2)") (class "Default")
      (node (ref "R21") (pin "2") (pinfunction "PIN2_2") (pintype "passive"))
      (node (ref "S11") (pin "4") (pinfunction "anode_4") (pintype "passive"))
    )
    (net (code "68") (name "Net-(R23-PIN2)") (class "Default")
      (node (ref "R23") (pin "2") (pinfunction "PIN2_2") (pintype "passive"))
      (node (ref "S12") (pin "4") (pinfunction "anode_4") (pintype "passive"))
    )
    (net (code "69") (name "Net-(R25-PIN2)") (class "Default")
      (node (ref "R25") (pin "2") (pinfunction "PIN2_2") (pintype "passive"))
      (node (ref "S13") (pin "4") (pinfunction "anode_4") (pintype "passive"))
    )
    (net (code "70") (name "Net-(R27-PIN2)") (class "Default")
      (node (ref "R27") (pin "2") (pinfunction "PIN2_2") (pintype "passive"))
      (node (ref "S14") (pin "4") (pinfunction "anode_4") (pintype "passive"))
    )
    (net (code "71") (name "Net-(R29-PIN2)") (class "Default")
      (node (ref "R29") (pin "2") (pinfunction "PIN2_2") (pintype "passive"))
      (node (ref "S15") (pin "4") (pinfunction "anode_4") (pintype "passive"))
    )
    (net (code "72") (name "Net-(R31-PIN2)") (class "Default")
      (node (ref "R31") (pin "2") (pinfunction "PIN2_2") (pintype "passive"))
      (node (ref "S16") (pin "4") (pinfunction "anode_4") (pintype "passive"))
    )
    (net (code "73") (name "Net-(R33-PIN2)") (class "Default")
      (node (ref "R33") (pin "2") (pinfunction "PIN2_2") (pintype "passive"))
      (node (ref "S17") (pin "4") (pinfunction "anode_4") (pintype "passive"))
    )
    (net (code "74") (name "Net-(R35-PIN2)") (class "Default")
      (node (ref "R35") (pin "2") (pinfunction "PIN2_2") (pintype "passive"))
      (node (ref "S18") (pin "4") (pinfunction "anode_4") (pintype "passive"))
    )
    (net (code "75") (name "Net-(R37-PIN2)") (class "Default")
      (node (ref "R37") (pin "2") (pinfunction "PIN2_2") (pintype "passive"))
      (node (ref "S19") (pin "4") (pinfunction "anode_4") (pintype "passive"))
    )
    (net (code "76") (name "Net-(R39-PIN2)") (class "Default")
      (node (ref "R39") (pin "2") (pinfunction "PIN2_2") (pintype "passive"))
      (node (ref "S20") (pin "4") (pinfunction "anode_4") (pintype "passive"))
    )
    (net (code "77") (name "Net-(R41-PIN2)") (class "Default")
      (node (ref "R41") (pin "2") (pinfunction "PIN2_2") (pintype "passive"))
      (node (ref "S21") (pin "4") (pinfunction "anode_4") (pintype "passive"))
    )
    (net (code "78") (name "Net-(R43-PIN2)") (class "Default")
      (node (ref "R43") (pin "2") (pinfunction "PIN2_2") (pintype "passive"))
      (node (ref "S22") (pin "4") (pinfunction "anode_4") (pintype "passive"))
    )
    (net (code "79") (name "Net-(R45-PIN2)") (class "Default")
      (node (ref "R45") (pin "2") (pinfunction "PIN2_2") (pintype "passive"))
      (node (ref "S23") (pin "4") (pinfunction "anode_4") (pintype "passive"))
    )
    (net (code "80") (name "Net-(R47-PIN2)") (class "Default")
      (node (ref "R47") (pin "2") (pinfunction "PIN2_2") (pintype "passive"))
      (node (ref "S24") (pin "4") (pinfunction "anode_4") (pintype "passive"))
    )
    (net (code "81") (name "Net-(R49-PIN2)") (class "Default")
      (node (ref "R49") (pin "2") (pinfunction "PIN2_2") (pintype "passive"))
      (node (ref "S25") (pin "4") (pinfunction "anode_4") (pintype "passive"))
    )
    (net (code "82") (name "Net-(R51-PIN2)") (class "Default")
      (node (ref "R51") (pin "2") (pinfunction "PIN2_2") (pintype "passive"))
      (node (ref "S26") (pin "4") (pinfunction "anode_4") (pintype "passive"))
    )
    (net (code "83") (name "unconnected-(Arduino_nano-3V3-Pad17)") (class "Default")
      (node (ref "Arduino_nano") (pin "17") (pinfunction "3V3_17") (pintype "power_in+no_connect"))
    )
    (net (code "84") (name "unconnected-(Arduino_nano-AREF-Pad18)") (class "Default")
      (node (ref "Arduino_nano") (pin "18") (pinfunction "AREF_18") (pintype "power_in+no_connect"))
    )
    (net (code "85") (name "unconnected-(Arduino_nano-RESET-Pad3)") (class "Default")
      (node (ref "Arduino_nano") (pin "3") (pinfunction "RESET_3") (pintype "input+no_connect"))
    )
    (net (code "86") (name "unconnected-(Arduino_nano-RESET-Pad28)") (class "Default")
      (node (ref "Arduino_nano") (pin "28") (pinfunction "RESET_28") (pintype "input+no_connect"))
    )
    (net (code "87") (name "unconnected-(Arduino_nano-VIN-Pad30)") (class "Default")
      (node (ref "Arduino_nano") (pin "30") (pinfunction "VIN_30") (pintype "input+no_connect"))
    )
    (net (code "88") (name "unconnected-(XT60-M-POS-PadP)") (class "Default")
      (node (ref "XT60-M") (pin "P") (pinfunction "POS_P") (pintype "passive"))
    )
  )
)
